# Artemis_Plus.net
KiCad netlist of a schematic drawn in Altium Designer
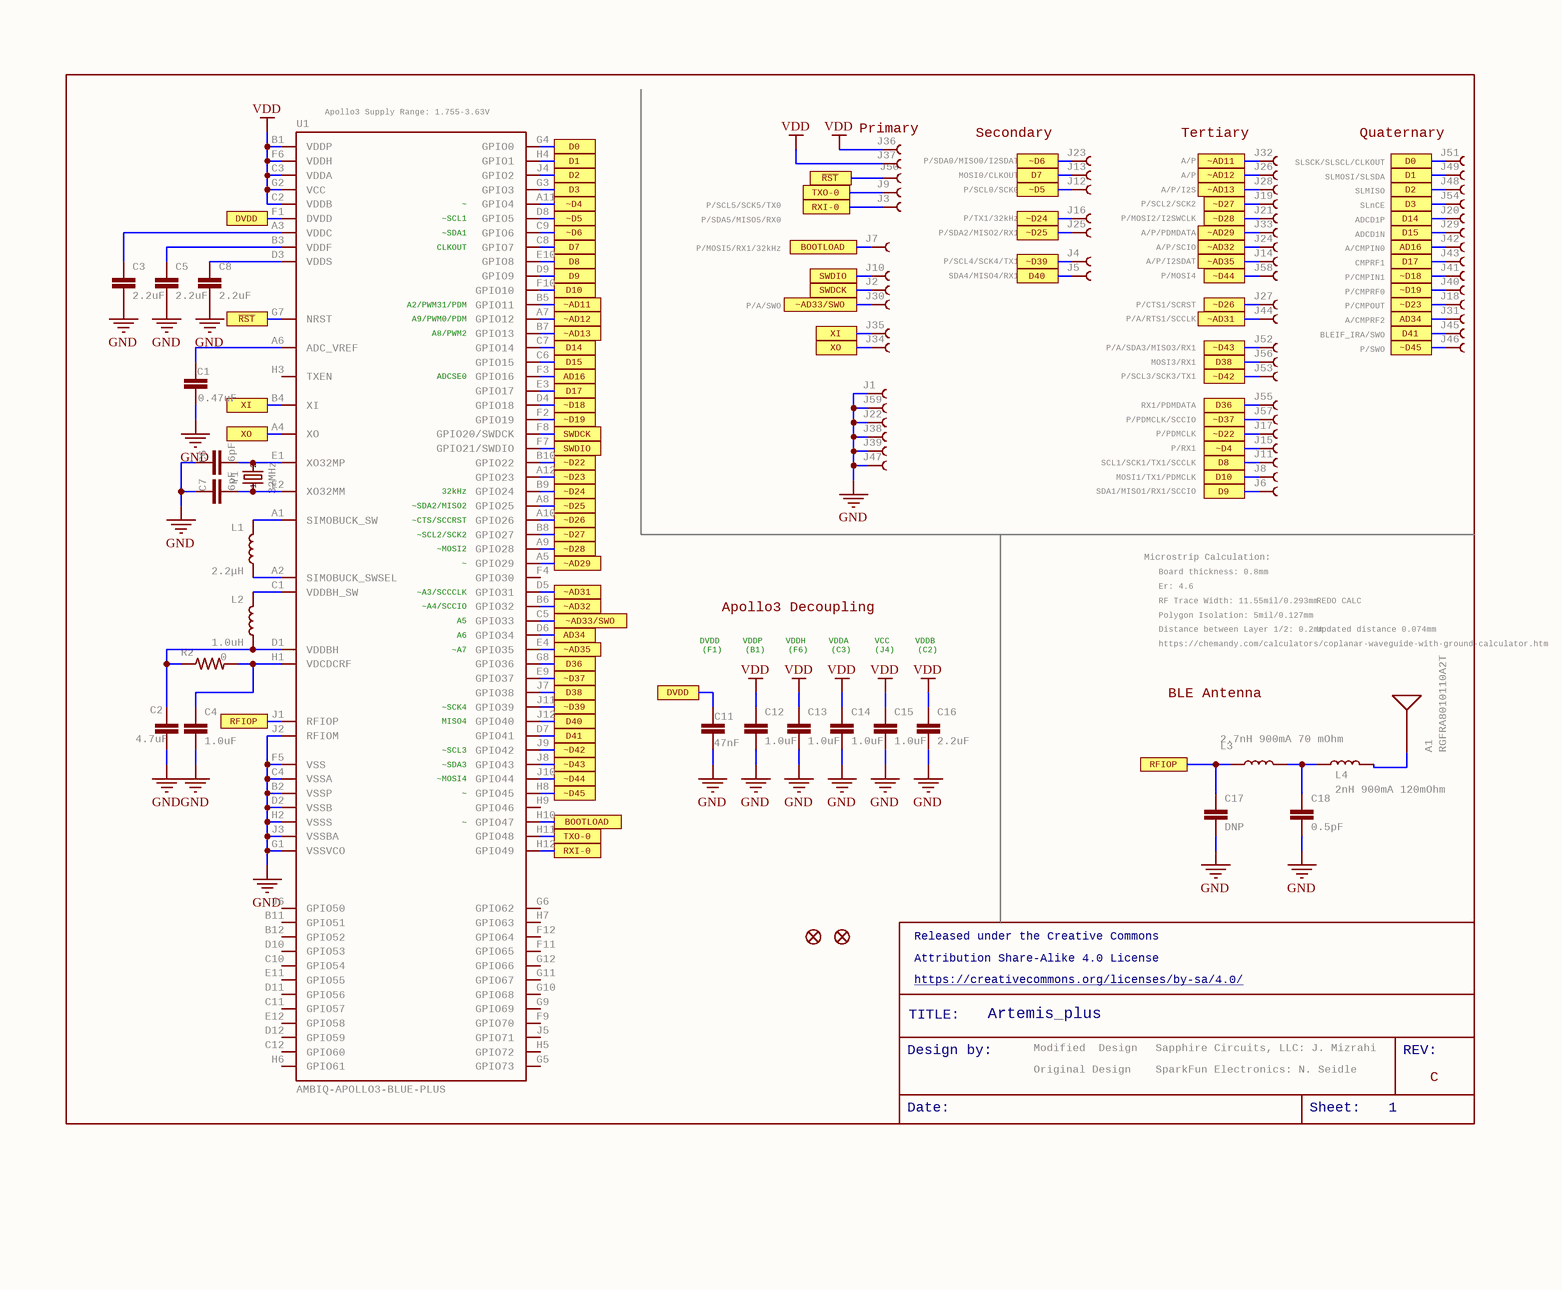
[diagram p0: Artemis_Plus.SchDoc]

(export (version "E")
  (design (tool "Eeschema 10.0.6"))
  (components
    (comp (ref "A1")
      (value "RGFRA8010110A2T")
      (footprint "RGFRA8010110A2T")
      (description "Chip Antenna, 2.45Ghz, Smt Rohs Compliant: Yes ¦Walsin RGFRA8010110A2T")
      (fields (field (name "MANUFACTURER") "Walsin Technologies"))
      (libsource (lib "Artemis_Plus") (part "RGFRA8010110A2T"))
    )
    (comp (ref "C1")
      (value "0.47uF")
      (footprint "0402-TIGHT-C")
      (description "Multilayer Ceramic Capacitor, 0.47 uF, 50 V, ± 2%, C0G (NP0), 0402 [1005 Metric]")
      (fields
        (field (name "MANUFACTURER") "Yageo")
        (field (name "MANUFACTURER PART NUMBER") "CC0402KRX7R6BB474")
      )
      (libsource (lib "Artemis_Plus") (part "CC0402KRX7R6BB474"))
    )
    (comp (ref "C2")
      (value "4.7uF")
      (footprint "0402-TIGHT-C")
      (description "Multilayer Ceramic Capacitor, 4.7 uF, 10 V, ± 20%, X5R, 0402 [1005 Metric]")
      (fields
        (field (name "MANUFACTURER") "Samsung")
        (field (name "MANUFACTURER PART NUMBER") "CL05A475MP5NRNC")
      )
      (libsource (lib "Artemis_Plus") (part "CL05A475MP5NRNC"))
    )
    (comp (ref "C3")
      (value "2.2uF")
      (footprint "0402-TIGHT-C")
      (description "Multilayer Ceramic Capacitor, 2.2 uF, 10 V, ± 10%, X5R, 0402 [1005 Metric]")
      (fields
        (field (name "MANUFACTURER") "Murata")
        (field (name "MANUFACTURER PART NUMBER") "GRM155R61A225KE01D")
      )
      (libsource (lib "Artemis_Plus") (part "GRM155R61A225KE01D"))
    )
    (comp (ref "C4")
      (value "1.0uF")
      (footprint "0402-TIGHT-C")
      (description "Multilayer Ceramic Capacitor, 1 uF, 6.3 V, ± 10%, X7R, 0402 [1005 Metric]")
      (fields
        (field (name "MANUFACTURER") "Murata")
        (field (name "MANUFACTURER PART NUMBER") "GRM155R70J105KA12J")
      )
      (libsource (lib "Artemis_Plus") (part "GRM155R70J105KA12J"))
    )
    (comp (ref "C5")
      (value "2.2uF")
      (footprint "0402-TIGHT-C")
      (description "Multilayer Ceramic Capacitor, 2.2 uF, 10 V, ± 10%, X5R, 0402 [1005 Metric]")
      (fields
        (field (name "MANUFACTURER") "Murata")
        (field (name "MANUFACTURER PART NUMBER") "GRM155R61A225KE01D")
      )
      (libsource (lib "Artemis_Plus") (part "GRM155R61A225KE01D"))
    )
    (comp (ref "C6")
      (value "6pF")
      (footprint "0402-TIGHT-C")
      (description "0402 6 pF 50 V ±0.5 pF Tolerance C0G/NP0 SMT Multilayer Ceramic Capacitor")
      (fields
        (field (name "MANUFACTURER") "Walsin Technologies")
        (field (name "MANUFACTURER PART NUMBER") "0402N6R0D500CT")
      )
      (libsource (lib "Artemis_Plus") (part "0402N6R0D500CT"))
    )
    (comp (ref "C7")
      (value "6pF")
      (footprint "0402-TIGHT-C")
      (description "0402 6 pF 50 V ±0.5 pF Tolerance C0G/NP0 SMT Multilayer Ceramic Capacitor")
      (fields
        (field (name "MANUFACTURER") "Walsin Technologies")
        (field (name "MANUFACTURER PART NUMBER") "0402N6R0D500CT")
      )
      (libsource (lib "Artemis_Plus") (part "0402N6R0D500CT"))
    )
    (comp (ref "C8")
      (value "2.2uF")
      (footprint "0402-TIGHT-C")
      (description "Multilayer Ceramic Capacitor, 2.2 uF, 10 V, ± 10%, X5R, 0402 [1005 Metric]")
      (fields
        (field (name "MANUFACTURER") "Murata")
        (field (name "MANUFACTURER PART NUMBER") "GRM155R61A225KE01D")
      )
      (libsource (lib "Artemis_Plus") (part "GRM155R61A225KE01D"))
    )
    (comp (ref "C11")
      (value "47nF")
      (footprint "0402-TIGHT-C")
      (description "CAP CER 0.047UF 16V 10% X7R 0402")
      (fields
        (field (name "MANUFACTURER") "Murata")
        (field (name "MANUFACTURER PART NUMBER") "GCM155R71C473KA37D")
      )
      (libsource (lib "Artemis_Plus") (part "GCM155R71C473KA37D"))
    )
    (comp (ref "C12")
      (value "1.0uF")
      (footprint "0402-TIGHT-C")
      (description "Multilayer Ceramic Capacitor, 1 uF, 6.3 V, ± 10%, X7R, 0402 [1005 Metric]")
      (fields
        (field (name "MANUFACTURER") "Murata")
        (field (name "MANUFACTURER PART NUMBER") "GRM155R70J105KA12J")
      )
      (libsource (lib "Artemis_Plus") (part "GRM155R70J105KA12J"))
    )
    (comp (ref "C13")
      (value "1.0uF")
      (footprint "0402-TIGHT-C")
      (description "Multilayer Ceramic Capacitor, 1 uF, 6.3 V, ± 10%, X7R, 0402 [1005 Metric]")
      (fields
        (field (name "MANUFACTURER") "Murata")
        (field (name "MANUFACTURER PART NUMBER") "GRM155R70J105KA12J")
      )
      (libsource (lib "Artemis_Plus") (part "GRM155R70J105KA12J"))
    )
    (comp (ref "C14")
      (value "1.0uF")
      (footprint "0402-TIGHT-C")
      (description "Multilayer Ceramic Capacitor, 1 uF, 6.3 V, ± 10%, X7R, 0402 [1005 Metric]")
      (fields
        (field (name "MANUFACTURER") "Murata")
        (field (name "MANUFACTURER PART NUMBER") "GRM155R70J105KA12J")
      )
      (libsource (lib "Artemis_Plus") (part "GRM155R70J105KA12J"))
    )
    (comp (ref "C15")
      (value "1.0uF")
      (footprint "0402-TIGHT-C")
      (description "Multilayer Ceramic Capacitor, 1 uF, 6.3 V, ± 10%, X7R, 0402 [1005 Metric]")
      (fields
        (field (name "MANUFACTURER") "Murata")
        (field (name "MANUFACTURER PART NUMBER") "GRM155R70J105KA12J")
      )
      (libsource (lib "Artemis_Plus") (part "GRM155R70J105KA12J"))
    )
    (comp (ref "C16")
      (value "2.2uF")
      (footprint "0402-TIGHT-C")
      (description "Multilayer Ceramic Capacitor, 2.2 uF, 10 V, ± 10%, X5R, 0402 [1005 Metric]")
      (fields
        (field (name "MANUFACTURER") "Murata")
        (field (name "MANUFACTURER PART NUMBER") "GRM155R61A225KE01D")
      )
      (libsource (lib "Artemis_Plus") (part "GRM155R61A225KE01D"))
    )
    (comp (ref "C17")
      (value "DNP")
      (footprint "0402-TIGHT")
      (libsource (lib "Artemis_Plus") (part "DNP-CAP-0402-TIGHT"))
    )
    (comp (ref "C18")
      (value "0.5pF")
      (footprint "0402-TIGHT-C")
      (description "Multilayer Ceramic Capacitor, 0.5 pF, 50 V, ± 0.25pF, C0G (NP0), 0402 [1005 Metric]")
      (fields
        (field (name "MANUFACTURER") "Murata")
        (field (name "MANUFACTURER PART NUMBER") "GJM1555C1HR50CB01D")
      )
      (libsource (lib "Artemis_Plus") (part "GJM1555C1HR50CB01D"))
    )
    (comp (ref "FD1")
      (value "FIDUCIAL0.4MM")
      (footprint "FIDUCIAL-0.4MM")
      (libsource (lib "Artemis_Plus") (part "FIDUCIAL0.4MM"))
    )
    (comp (ref "FD2")
      (value "FIDUCIAL0.4MM")
      (footprint "FIDUCIAL-0.4MM")
      (libsource (lib "Artemis_Plus") (part "FIDUCIAL0.4MM"))
    )
    (comp (ref "J1")
      (value "PAD.4X.6")
      (footprint "MODULE_PAD")
      (libsource (lib "Artemis_Plus") (part "PAD.4X.6"))
    )
    (comp (ref "J2")
      (value "PAD.4X.6")
      (footprint "MODULE_PAD")
      (libsource (lib "Artemis_Plus") (part "PAD.4X.6"))
    )
    (comp (ref "J3")
      (value "PAD.4X.6")
      (footprint "MODULE_PAD")
      (libsource (lib "Artemis_Plus") (part "PAD.4X.6"))
    )
    (comp (ref "J4")
      (value "PAD.4X.6")
      (footprint "MODULE_PAD")
      (libsource (lib "Artemis_Plus") (part "PAD.4X.6"))
    )
    (comp (ref "J5")
      (value "PAD.4X.6")
      (footprint "MODULE_PAD")
      (libsource (lib "Artemis_Plus") (part "PAD.4X.6"))
    )
    (comp (ref "J6")
      (value "PAD.4X.6")
      (footprint "MODULE_PAD")
      (libsource (lib "Artemis_Plus") (part "PAD.4X.6"))
    )
    (comp (ref "J7")
      (value "PAD.4X.6")
      (footprint "MODULE_PAD")
      (libsource (lib "Artemis_Plus") (part "PAD.4X.6"))
    )
    (comp (ref "J8")
      (value "PAD.4X.6")
      (footprint "MODULE_PAD")
      (libsource (lib "Artemis_Plus") (part "PAD.4X.6"))
    )
    (comp (ref "J9")
      (value "PAD.4X.6")
      (footprint "MODULE_PAD")
      (libsource (lib "Artemis_Plus") (part "PAD.4X.6"))
    )
    (comp (ref "J10")
      (value "PAD.4X.6")
      (footprint "MODULE_PAD")
      (libsource (lib "Artemis_Plus") (part "PAD.4X.6"))
    )
    (comp (ref "J11")
      (value "PAD.4X.6")
      (footprint "MODULE_PAD")
      (libsource (lib "Artemis_Plus") (part "PAD.4X.6"))
    )
    (comp (ref "J12")
      (value "PAD.4X.6")
      (footprint "MODULE_PAD")
      (libsource (lib "Artemis_Plus") (part "PAD.4X.6"))
    )
    (comp (ref "J13")
      (value "PAD.4X.6")
      (footprint "MODULE_PAD")
      (libsource (lib "Artemis_Plus") (part "PAD.4X.6"))
    )
    (comp (ref "J14")
      (value "PAD.4X.6")
      (footprint "MODULE_PAD")
      (libsource (lib "Artemis_Plus") (part "PAD.4X.6"))
    )
    (comp (ref "J15")
      (value "PAD.4X.6")
      (footprint "MODULE_PAD")
      (libsource (lib "Artemis_Plus") (part "PAD.4X.6"))
    )
    (comp (ref "J16")
      (value "PAD.4X.6")
      (footprint "MODULE_PAD")
      (libsource (lib "Artemis_Plus") (part "PAD.4X.6"))
    )
    (comp (ref "J17")
      (value "PAD.4X.6")
      (footprint "MODULE_PAD")
      (libsource (lib "Artemis_Plus") (part "PAD.4X.6"))
    )
    (comp (ref "J18")
      (value "PAD.4X.6")
      (footprint "MODULE_PAD")
      (libsource (lib "Artemis_Plus") (part "PAD.4X.6"))
    )
    (comp (ref "J19")
      (value "PAD.4X.6")
      (footprint "MODULE_PAD")
      (libsource (lib "Artemis_Plus") (part "PAD.4X.6"))
    )
    (comp (ref "J20")
      (value "PAD.4X.6")
      (footprint "MODULE_PAD")
      (libsource (lib "Artemis_Plus") (part "PAD.4X.6"))
    )
    (comp (ref "J21")
      (value "PAD.4X.6")
      (footprint "MODULE_PAD")
      (libsource (lib "Artemis_Plus") (part "PAD.4X.6"))
    )
    (comp (ref "J22")
      (value "~")
      (footprint "MODULE_MINI_PAD")
      (libsource (lib "Artemis_Plus") (part "PAD.6X.6"))
    )
    (comp (ref "J23")
      (value "PAD.4X.6")
      (footprint "MODULE_PAD")
      (libsource (lib "Artemis_Plus") (part "PAD.4X.6"))
    )
    (comp (ref "J24")
      (value "PAD.4X.6")
      (footprint "MODULE_PAD")
      (libsource (lib "Artemis_Plus") (part "PAD.4X.6"))
    )
    (comp (ref "J25")
      (value "PAD.4X.6")
      (footprint "MODULE_PAD")
      (libsource (lib "Artemis_Plus") (part "PAD.4X.6"))
    )
    (comp (ref "J26")
      (value "PAD.4X.6")
      (footprint "MODULE_PAD")
      (libsource (lib "Artemis_Plus") (part "PAD.4X.6"))
    )
    (comp (ref "J27")
      (value "PAD.4X.6")
      (footprint "MODULE_PAD")
      (libsource (lib "Artemis_Plus") (part "PAD.4X.6"))
    )
    (comp (ref "J28")
      (value "PAD.4X.6")
      (footprint "MODULE_PAD")
      (libsource (lib "Artemis_Plus") (part "PAD.4X.6"))
    )
    (comp (ref "J29")
      (value "PAD.4X.6")
      (footprint "MODULE_PAD")
      (libsource (lib "Artemis_Plus") (part "PAD.4X.6"))
    )
    (comp (ref "J30")
      (value "PAD.4X.6")
      (footprint "MODULE_PAD")
      (libsource (lib "Artemis_Plus") (part "PAD.4X.6"))
    )
    (comp (ref "J31")
      (value "PAD.4X.6")
      (footprint "MODULE_PAD")
      (libsource (lib "Artemis_Plus") (part "PAD.4X.6"))
    )
    (comp (ref "J32")
      (value "PAD.4X.6")
      (footprint "MODULE_PAD")
      (libsource (lib "Artemis_Plus") (part "PAD.4X.6"))
    )
    (comp (ref "J33")
      (value "PAD.4X.6")
      (footprint "MODULE_PAD")
      (libsource (lib "Artemis_Plus") (part "PAD.4X.6"))
    )
    (comp (ref "J34")
      (value "PAD.4X.6")
      (footprint "MODULE_PAD")
      (libsource (lib "Artemis_Plus") (part "PAD.4X.6"))
    )
    (comp (ref "J35")
      (value "PAD.4X.6")
      (footprint "MODULE_PAD")
      (libsource (lib "Artemis_Plus") (part "PAD.4X.6"))
    )
    (comp (ref "J36")
      (value "PAD.4X.6")
      (footprint "MODULE_PAD")
      (libsource (lib "Artemis_Plus") (part "PAD.4X.6"))
    )
    (comp (ref "J37")
      (value "PAD.4X.6")
      (footprint "MODULE_PAD")
      (libsource (lib "Artemis_Plus") (part "PAD.4X.6"))
    )
    (comp (ref "J38")
      (value "PAD.6X.6")
      (footprint "MODULE_MINI_PAD")
      (libsource (lib "Artemis_Plus") (part "PAD.6X.6"))
    )
    (comp (ref "J39")
      (value "PAD.4X.6")
      (footprint "MODULE_PAD")
      (libsource (lib "Artemis_Plus") (part "PAD.4X.6"))
    )
    (comp (ref "J40")
      (value "PAD.4X.6")
      (footprint "MODULE_PAD")
      (libsource (lib "Artemis_Plus") (part "PAD.4X.6"))
    )
    (comp (ref "J41")
      (value "PAD.4X.6")
      (footprint "MODULE_PAD")
      (libsource (lib "Artemis_Plus") (part "PAD.4X.6"))
    )
    (comp (ref "J42")
      (value "PAD.4X.6")
      (footprint "MODULE_PAD")
      (libsource (lib "Artemis_Plus") (part "PAD.4X.6"))
    )
    (comp (ref "J43")
      (value "PAD.4X.6")
      (footprint "MODULE_PAD")
      (libsource (lib "Artemis_Plus") (part "PAD.4X.6"))
    )
    (comp (ref "J44")
      (value "PAD.4X.6")
      (footprint "MODULE_PAD")
      (libsource (lib "Artemis_Plus") (part "PAD.4X.6"))
    )
    (comp (ref "J45")
      (value "PAD.4X.6")
      (footprint "MODULE_PAD")
      (libsource (lib "Artemis_Plus") (part "PAD.4X.6"))
    )
    (comp (ref "J46")
      (value "PAD.4X.6")
      (footprint "MODULE_PAD")
      (libsource (lib "Artemis_Plus") (part "PAD.4X.6"))
    )
    (comp (ref "J47")
      (value "PAD.4X.6")
      (footprint "MODULE_PAD")
      (libsource (lib "Artemis_Plus") (part "PAD.4X.6"))
    )
    (comp (ref "J48")
      (value "PAD.4X.6")
      (footprint "MODULE_PAD")
      (libsource (lib "Artemis_Plus") (part "PAD.4X.6"))
    )
    (comp (ref "J49")
      (value "PAD.4X.6")
      (footprint "MODULE_PAD")
      (libsource (lib "Artemis_Plus") (part "PAD.4X.6"))
    )
    (comp (ref "J50")
      (value "PAD.4X.6")
      (footprint "MODULE_PAD")
      (libsource (lib "Artemis_Plus") (part "PAD.4X.6"))
    )
    (comp (ref "J51")
      (value "PAD.4X.6")
      (footprint "MODULE_PAD")
      (libsource (lib "Artemis_Plus") (part "PAD.4X.6"))
    )
    (comp (ref "J52")
      (value "PAD.4X.6")
      (footprint "MODULE_PAD")
      (libsource (lib "Artemis_Plus") (part "PAD.4X.6"))
    )
    (comp (ref "J53")
      (value "PAD.4X.6")
      (footprint "MODULE_PAD")
      (libsource (lib "Artemis_Plus") (part "PAD.4X.6"))
    )
    (comp (ref "J54")
      (value "PAD.4X.6")
      (footprint "MODULE_PAD")
      (libsource (lib "Artemis_Plus") (part "PAD.4X.6"))
    )
    (comp (ref "J55")
      (value "PAD.4X.6")
      (footprint "MODULE_PAD")
      (libsource (lib "Artemis_Plus") (part "PAD.4X.6"))
    )
    (comp (ref "J56")
      (value "PAD.4X.6")
      (footprint "MODULE_PAD")
      (libsource (lib "Artemis_Plus") (part "PAD.4X.6"))
    )
    (comp (ref "J57")
      (value "PAD.4X.6")
      (footprint "MODULE_PAD")
      (libsource (lib "Artemis_Plus") (part "PAD.4X.6"))
    )
    (comp (ref "J58")
      (value "PAD.4X.6")
      (footprint "MODULE_PAD")
      (libsource (lib "Artemis_Plus") (part "PAD.4X.6"))
    )
    (comp (ref "J59")
      (value "PAD.4X.6")
      (footprint "MODULE_PAD")
      (libsource (lib "Artemis_Plus") (part "PAD.4X.6"))
    )
    (comp (ref "L1")
      (value "2.2μH")
      (footprint "DFE201610E-2R2MP2")
      (description "Inductor Power Shielded Wirewound 2.2uH 20% 1MHz Metal 1.7A 0.14Ohm DCR 0806 T/R")
      (fields
        (field (name "MANUFACTURER") "Murata")
        (field (name "MANUFACTURER PART NUMBER") "DFE201610E-2R2M=P2")
      )
      (libsource (lib "Artemis_Plus") (part "DFE201610E-2R2M=P2"))
    )
    (comp (ref "L2")
      (value "1.0uH")
      (footprint "LQM21PN1R0MEHD")
      (description "Inductor Power Chip Shielded Multi-Layer 1uH 20% 1MHz Ferrite 1.6A 0.107Ohm DCR 0805 T/R")
      (fields
        (field (name "MANUFACTURER") "Murata")
        (field (name "MANUFACTURER PART NUMBER") "LQM21PN1R0MEHD")
      )
      (libsource (lib "Artemis_Plus") (part "LQM21PN1R0MEHD"))
    )
    (comp (ref "L3")
      (value "2.7nH 900mA 70 mOhm")
      (footprint "0402-TIGHT-L")
      (description "IND 2.7NH 900MA 70 MOHM")
      (fields
        (field (name "MANUFACTURER") "Murata")
        (field (name "MANUFACTURER PART NUMBER") "LQG15WZ2N7S02D")
      )
      (libsource (lib "Artemis_Plus") (part "LQG15WZ2N7S02D"))
    )
    (comp (ref "L4")
      (value "2nH 900mA 120mOhm")
      (footprint "0402-TIGHT-L")
      (description "FIXED IND 2NH 900MA 120 MOHM SMD")
      (fields
        (field (name "MANUFACTURER") "Murata")
        (field (name "MANUFACTURER PART NUMBER") "LQG15HN2N0S02D")
      )
      (libsource (lib "Artemis_Plus") (part "LQG15HN2N0S02D"))
    )
    (comp (ref "R2")
      (value "0")
      (footprint "0402-TIGHT-R")
      (description "Res Thick Film 0402 0 Ohm Jumper Molded SMD Paper T/R")
      (fields
        (field (name "MANUFACTURER") "Stackpole Electronics")
        (field (name "MANUFACTURER PART NUMBER") "RMCF0402ZT0R00")
      )
      (libsource (lib "Artemis_Plus") (part "RMCF0402ZT0R00"))
    )
    (comp (ref "U1")
      (value "AMBIQ-APOLLO3-BLUE-PLUS")
      (footprint "BGA-104-5.3X4.3MM - Sprite-mixed-0.2-0.19 - 3DModel")
      (description "Apollo3 Blue Plus 96 MHz Cortex M4F, 2048 KB Flash, 768 KB RAM, BLE 5, BGA")
      (fields
        (field (name "MANUFACTURER") "Ambiq Micro")
        (field (name "MANUFACTURER PART NUMBER") "AMA3B2KK-KBR")
      )
      (libsource (lib "Artemis_Plus") (part "AMA3B2KK-KBR"))
    )
    (comp (ref "Y1")
      (value "32MHz")
      (footprint "ECS-320-6-37B2-CKM-TR")
      (description "Crystal 32 Mhz 6PF SMD")
      (fields
        (field (name "MANUFACTURER") "ECS International")
        (field (name "MANUFACTURER PART NUMBER") "ECS-320-6-37B2-CKM-TR")
        (field (name "1") "1")
        (field (name "2") "2")
      )
      (libsource (lib "Artemis_Plus") (part "ECS-320-6-37B2-CKM-TR"))
    )
  )
  (nets
    (net (code "1") (name "/AD16") (class "Default")
      (node (ref "J42") (pin "1") (pinfunction "1_1") (pintype "bidirectional"))
      (node (ref "U1") (pin "F3") (pinfunction "GPIO16_F3") (pintype "bidirectional"))
    )
    (net (code "2") (name "/AD34") (class "Default")
      (node (ref "J31") (pin "1") (pinfunction "1_1") (pintype "bidirectional"))
      (node (ref "U1") (pin "D6") (pinfunction "GPIO34_D6") (pintype "bidirectional"))
    )
    (net (code "3") (name "/BOOTLOAD") (class "Default")
      (node (ref "J7") (pin "1") (pinfunction "1_1") (pintype "bidirectional"))
      (node (ref "U1") (pin "H10") (pinfunction "GPIO47_H10") (pintype "bidirectional"))
    )
    (net (code "4") (name "/D0") (class "Default")
      (node (ref "J51") (pin "1") (pinfunction "1_1") (pintype "bidirectional"))
      (node (ref "U1") (pin "G4") (pinfunction "GPIO0_G4") (pintype "bidirectional"))
    )
    (net (code "5") (name "/D1") (class "Default")
      (node (ref "J49") (pin "1") (pinfunction "1_1") (pintype "bidirectional"))
      (node (ref "U1") (pin "H4") (pinfunction "GPIO1_H4") (pintype "bidirectional"))
    )
    (net (code "6") (name "/D2") (class "Default")
      (node (ref "J48") (pin "1") (pinfunction "1_1") (pintype "bidirectional"))
      (node (ref "U1") (pin "J4") (pinfunction "GPIO2_J4") (pintype "bidirectional"))
    )
    (net (code "7") (name "/D3") (class "Default")
      (node (ref "J54") (pin "1") (pinfunction "1_1") (pintype "bidirectional"))
      (node (ref "U1") (pin "G3") (pinfunction "GPIO3_G3") (pintype "bidirectional"))
    )
    (net (code "8") (name "/D7") (class "Default")
      (node (ref "J13") (pin "1") (pinfunction "1_1") (pintype "bidirectional"))
      (node (ref "U1") (pin "C8") (pinfunction "GPIO7_C8") (pintype "bidirectional"))
    )
    (net (code "9") (name "/D8") (class "Default")
      (node (ref "J11") (pin "1") (pinfunction "1_1") (pintype "bidirectional"))
      (node (ref "U1") (pin "E10") (pinfunction "GPIO8_E10") (pintype "bidirectional"))
    )
    (net (code "10") (name "/D9") (class "Default")
      (node (ref "J6") (pin "1") (pinfunction "1_1") (pintype "bidirectional"))
      (node (ref "U1") (pin "D9") (pinfunction "GPIO9_D9") (pintype "bidirectional"))
    )
    (net (code "11") (name "/D10") (class "Default")
      (node (ref "J8") (pin "1") (pinfunction "1_1") (pintype "bidirectional"))
      (node (ref "U1") (pin "F10") (pinfunction "GPIO10_F10") (pintype "bidirectional"))
    )
    (net (code "12") (name "/D14") (class "Default")
      (node (ref "J20") (pin "1") (pinfunction "1_1") (pintype "bidirectional"))
      (node (ref "U1") (pin "C7") (pinfunction "GPIO14_C7") (pintype "bidirectional"))
    )
    (net (code "13") (name "/D15") (class "Default")
      (node (ref "J29") (pin "1") (pinfunction "1_1") (pintype "bidirectional"))
      (node (ref "U1") (pin "C6") (pinfunction "GPIO15_C6") (pintype "bidirectional"))
    )
    (net (code "14") (name "/D17") (class "Default")
      (node (ref "J43") (pin "1") (pinfunction "1_1") (pintype "bidirectional"))
      (node (ref "U1") (pin "E3") (pinfunction "GPIO17_E3") (pintype "bidirectional"))
    )
    (net (code "15") (name "/D36") (class "Default")
      (node (ref "J55") (pin "1") (pinfunction "1_1") (pintype "bidirectional"))
      (node (ref "U1") (pin "G8") (pinfunction "GPIO36_G8") (pintype "bidirectional"))
    )
    (net (code "16") (name "/D38") (class "Default")
      (node (ref "J56") (pin "1") (pinfunction "1_1") (pintype "bidirectional"))
      (node (ref "U1") (pin "J7") (pinfunction "GPIO38_J7") (pintype "bidirectional"))
    )
    (net (code "17") (name "/D40") (class "Default")
      (node (ref "J5") (pin "1") (pinfunction "1_1") (pintype "bidirectional"))
      (node (ref "U1") (pin "J12") (pinfunction "GPIO40_J12") (pintype "bidirectional"))
    )
    (net (code "18") (name "/D41") (class "Default")
      (node (ref "J45") (pin "1") (pinfunction "1_1") (pintype "bidirectional"))
      (node (ref "U1") (pin "D7") (pinfunction "GPIO41_D7") (pintype "bidirectional"))
    )
    (net (code "19") (name "/DVDD") (class "Default")
      (node (ref "C11") (pin "1") (pinfunction "1_1") (pintype "passive"))
      (node (ref "U1") (pin "F1") (pinfunction "DVDD_F1") (pintype "bidirectional"))
    )
    (net (code "20") (name "/RFIOP") (class "Default")
      (node (ref "C17") (pin "1") (pinfunction "1_1") (pintype "passive"))
      (node (ref "L3") (pin "1") (pinfunction "1_1") (pintype "passive"))
      (node (ref "U1") (pin "J1") (pinfunction "RFIOP_J1") (pintype "bidirectional"))
    )
    (net (code "21") (name "/RXI-0") (class "Default")
      (node (ref "J3") (pin "1") (pinfunction "1_1") (pintype "bidirectional"))
      (node (ref "U1") (pin "H12") (pinfunction "GPIO49_H12") (pintype "bidirectional"))
    )
    (net (code "22") (name "/SWDCK") (class "Default")
      (node (ref "J2") (pin "1") (pinfunction "1_1") (pintype "bidirectional"))
      (node (ref "U1") (pin "F8") (pinfunction "GPIO20/SWDCK_F8") (pintype "bidirectional"))
    )
    (net (code "23") (name "/SWDIO") (class "Default")
      (node (ref "J10") (pin "1") (pinfunction "1_1") (pintype "bidirectional"))
      (node (ref "U1") (pin "F7") (pinfunction "GPIO21/SWDIO_F7") (pintype "bidirectional"))
    )
    (net (code "24") (name "/TXO-0") (class "Default")
      (node (ref "J9") (pin "1") (pinfunction "1_1") (pintype "bidirectional"))
      (node (ref "U1") (pin "H11") (pinfunction "GPIO48_H11") (pintype "bidirectional"))
    )
    (net (code "25") (name "/XI") (class "Default")
      (node (ref "J35") (pin "1") (pinfunction "1_1") (pintype "bidirectional"))
      (node (ref "U1") (pin "B4") (pinfunction "XI_B4") (pintype "bidirectional"))
    )
    (net (code "26") (name "/XO") (class "Default")
      (node (ref "J34") (pin "1") (pinfunction "1_1") (pintype "bidirectional"))
      (node (ref "U1") (pin "A4") (pinfunction "XO_A4") (pintype "bidirectional"))
    )
    (net (code "27") (name "/~AD11") (class "Default")
      (node (ref "J32") (pin "1") (pinfunction "1_1") (pintype "bidirectional"))
      (node (ref "U1") (pin "B5") (pinfunction "GPIO11_B5") (pintype "bidirectional"))
    )
    (net (code "28") (name "/~AD12") (class "Default")
      (node (ref "J26") (pin "1") (pinfunction "1_1") (pintype "bidirectional"))
      (node (ref "U1") (pin "A7") (pinfunction "GPIO12_A7") (pintype "bidirectional"))
    )
    (net (code "29") (name "/~AD13") (class "Default")
      (node (ref "J28") (pin "1") (pinfunction "1_1") (pintype "bidirectional"))
      (node (ref "U1") (pin "B7") (pinfunction "GPIO13_B7") (pintype "bidirectional"))
    )
    (net (code "30") (name "/~AD29") (class "Default")
      (node (ref "J33") (pin "1") (pinfunction "1_1") (pintype "bidirectional"))
      (node (ref "U1") (pin "A5") (pinfunction "GPIO29_A5") (pintype "bidirectional"))
    )
    (net (code "31") (name "/~AD31") (class "Default")
      (node (ref "J44") (pin "1") (pinfunction "1_1") (pintype "bidirectional"))
      (node (ref "U1") (pin "D5") (pinfunction "GPIO31_D5") (pintype "bidirectional"))
    )
    (net (code "32") (name "/~AD32") (class "Default")
      (node (ref "J24") (pin "1") (pinfunction "1_1") (pintype "bidirectional"))
      (node (ref "U1") (pin "B6") (pinfunction "GPIO32_B6") (pintype "bidirectional"))
    )
    (net (code "33") (name "/~AD33{slash}SWO") (class "Default")
      (node (ref "J30") (pin "1") (pinfunction "1_1") (pintype "bidirectional"))
      (node (ref "U1") (pin "C5") (pinfunction "GPIO33_C5") (pintype "bidirectional"))
    )
    (net (code "34") (name "/~AD35") (class "Default")
      (node (ref "J14") (pin "1") (pinfunction "1_1") (pintype "bidirectional"))
      (node (ref "U1") (pin "E4") (pinfunction "GPIO35_E4") (pintype "bidirectional"))
    )
    (net (code "35") (name "/~D4") (class "Default")
      (node (ref "J15") (pin "1") (pinfunction "1_1") (pintype "bidirectional"))
      (node (ref "U1") (pin "A11") (pinfunction "GPIO4_A11") (pintype "bidirectional"))
    )
    (net (code "36") (name "/~D5") (class "Default")
      (node (ref "J12") (pin "1") (pinfunction "1_1") (pintype "bidirectional"))
      (node (ref "U1") (pin "D8") (pinfunction "GPIO5_D8") (pintype "bidirectional"))
    )
    (net (code "37") (name "/~D6") (class "Default")
      (node (ref "J23") (pin "1") (pinfunction "1_1") (pintype "bidirectional"))
      (node (ref "U1") (pin "C9") (pinfunction "GPIO6_C9") (pintype "bidirectional"))
    )
    (net (code "38") (name "/~D18") (class "Default")
      (node (ref "J41") (pin "1") (pinfunction "1_1") (pintype "bidirectional"))
      (node (ref "U1") (pin "D4") (pinfunction "GPIO18_D4") (pintype "bidirectional"))
    )
    (net (code "39") (name "/~D19") (class "Default")
      (node (ref "J40") (pin "1") (pinfunction "1_1") (pintype "bidirectional"))
      (node (ref "U1") (pin "F2") (pinfunction "GPIO19_F2") (pintype "bidirectional"))
    )
    (net (code "40") (name "/~D22") (class "Default")
      (node (ref "J17") (pin "1") (pinfunction "1_1") (pintype "bidirectional"))
      (node (ref "U1") (pin "B10") (pinfunction "GPIO22_B10") (pintype "bidirectional"))
    )
    (net (code "41") (name "/~D23") (class "Default")
      (node (ref "J18") (pin "1") (pinfunction "1_1") (pintype "bidirectional"))
      (node (ref "U1") (pin "A12") (pinfunction "GPIO23_A12") (pintype "bidirectional"))
    )
    (net (code "42") (name "/~D24") (class "Default")
      (node (ref "J16") (pin "1") (pinfunction "1_1") (pintype "bidirectional"))
      (node (ref "U1") (pin "B9") (pinfunction "GPIO24_B9") (pintype "bidirectional"))
    )
    (net (code "43") (name "/~D25") (class "Default")
      (node (ref "J25") (pin "1") (pinfunction "1_1") (pintype "bidirectional"))
      (node (ref "U1") (pin "A8") (pinfunction "GPIO25_A8") (pintype "bidirectional"))
    )
    (net (code "44") (name "/~D26") (class "Default")
      (node (ref "J27") (pin "1") (pinfunction "1_1") (pintype "bidirectional"))
      (node (ref "U1") (pin "A10") (pinfunction "GPIO26_A10") (pintype "bidirectional"))
    )
    (net (code "45") (name "/~D27") (class "Default")
      (node (ref "J19") (pin "1") (pinfunction "1_1") (pintype "bidirectional"))
      (node (ref "U1") (pin "B8") (pinfunction "GPIO27_B8") (pintype "bidirectional"))
    )
    (net (code "46") (name "/~D28") (class "Default")
      (node (ref "J21") (pin "1") (pinfunction "1_1") (pintype "bidirectional"))
      (node (ref "U1") (pin "A9") (pinfunction "GPIO28_A9") (pintype "bidirectional"))
    )
    (net (code "47") (name "/~D37") (class "Default")
      (node (ref "J57") (pin "1") (pinfunction "1_1") (pintype "bidirectional"))
      (node (ref "U1") (pin "E9") (pinfunction "GPIO37_E9") (pintype "bidirectional"))
    )
    (net (code "48") (name "/~D39") (class "Default")
      (node (ref "J4") (pin "1") (pinfunction "1_1") (pintype "bidirectional"))
      (node (ref "U1") (pin "J11") (pinfunction "GPIO39_J11") (pintype "bidirectional"))
    )
    (net (code "49") (name "/~D42") (class "Default")
      (node (ref "J53") (pin "1") (pinfunction "1_1") (pintype "bidirectional"))
      (node (ref "U1") (pin "J9") (pinfunction "GPIO42_J9") (pintype "bidirectional"))
    )
    (net (code "50") (name "/~D43") (class "Default")
      (node (ref "J52") (pin "1") (pinfunction "1_1") (pintype "bidirectional"))
      (node (ref "U1") (pin "J8") (pinfunction "GPIO43_J8") (pintype "bidirectional"))
    )
    (net (code "51") (name "/~D44") (class "Default")
      (node (ref "J58") (pin "1") (pinfunction "1_1") (pintype "bidirectional"))
      (node (ref "U1") (pin "J10") (pinfunction "GPIO44_J10") (pintype "bidirectional"))
    )
    (net (code "52") (name "/~D45") (class "Default")
      (node (ref "J46") (pin "1") (pinfunction "1_1") (pintype "bidirectional"))
      (node (ref "U1") (pin "H8") (pinfunction "GPIO45_H8") (pintype "bidirectional"))
    )
    (net (code "53") (name "/~{RST}") (class "Default")
      (node (ref "J50") (pin "1") (pinfunction "1_1") (pintype "bidirectional"))
      (node (ref "U1") (pin "G7") (pinfunction "NRST_G7") (pintype "bidirectional"))
    )
    (net (code "54") (name "GND") (class "Default")
      (node (ref "C1") (pin "2") (pinfunction "2_2") (pintype "passive"))
      (node (ref "C11") (pin "2") (pinfunction "2_2") (pintype "passive"))
      (node (ref "C12") (pin "2") (pinfunction "2_2") (pintype "passive"))
      (node (ref "C13") (pin "2") (pinfunction "2_2") (pintype "passive"))
      (node (ref "C14") (pin "2") (pinfunction "2_2") (pintype "passive"))
      (node (ref "C15") (pin "2") (pinfunction "2_2") (pintype "passive"))
      (node (ref "C16") (pin "2") (pinfunction "2_2") (pintype "passive"))
      (node (ref "C17") (pin "2") (pinfunction "2_2") (pintype "passive"))
      (node (ref "C18") (pin "2") (pinfunction "2_2") (pintype "passive"))
      (node (ref "C2") (pin "2") (pinfunction "2_2") (pintype "passive"))
      (node (ref "C3") (pin "2") (pinfunction "2_2") (pintype "passive"))
      (node (ref "C4") (pin "2") (pinfunction "2_2") (pintype "passive"))
      (node (ref "C5") (pin "2") (pinfunction "2_2") (pintype "passive"))
      (node (ref "C6") (pin "1") (pinfunction "1_1") (pintype "passive"))
      (node (ref "C7") (pin "1") (pinfunction "1_1") (pintype "passive"))
      (node (ref "C8") (pin "2") (pinfunction "2_2") (pintype "passive"))
      (node (ref "J1") (pin "1") (pinfunction "1_1") (pintype "bidirectional"))
      (node (ref "J22") (pin "1") (pinfunction "1_1") (pintype "bidirectional"))
      (node (ref "J38") (pin "1") (pinfunction "1_1") (pintype "bidirectional"))
      (node (ref "J39") (pin "1") (pinfunction "1_1") (pintype "bidirectional"))
      (node (ref "J47") (pin "1") (pinfunction "1_1") (pintype "bidirectional"))
      (node (ref "J59") (pin "1") (pinfunction "1_1") (pintype "bidirectional"))
      (node (ref "U1") (pin "B2") (pinfunction "VSSP_B2") (pintype "bidirectional"))
      (node (ref "U1") (pin "C4") (pinfunction "VSSA_C4") (pintype "bidirectional"))
      (node (ref "U1") (pin "D2") (pinfunction "VSSB_D2") (pintype "bidirectional"))
      (node (ref "U1") (pin "F5") (pinfunction "VSS_F5") (pintype "bidirectional"))
      (node (ref "U1") (pin "G1") (pinfunction "VSSVCO_G1") (pintype "bidirectional"))
      (node (ref "U1") (pin "H2") (pinfunction "VSSS_H2") (pintype "bidirectional"))
      (node (ref "U1") (pin "J2") (pinfunction "RFIOM_J2") (pintype "bidirectional"))
      (node (ref "U1") (pin "J3") (pinfunction "VSSBA_J3") (pintype "bidirectional"))
    )
    (net (code "55") (name "Net-(A1-SIGNAL)") (class "Default")
      (node (ref "A1") (pin "FEED") (pinfunction "SIGNAL_FEED") (pintype "bidirectional"))
      (node (ref "L4") (pin "2") (pinfunction "2_2") (pintype "passive"))
    )
    (net (code "56") (name "Net-(C18-Pad1)") (class "Default")
      (node (ref "C18") (pin "1") (pinfunction "1_1") (pintype "passive"))
      (node (ref "L3") (pin "2") (pinfunction "2_2") (pintype "passive"))
      (node (ref "L4") (pin "1") (pinfunction "1_1") (pintype "passive"))
    )
    (net (code "57") (name "Net-(U1-ADC_VREF)") (class "Default")
      (node (ref "C1") (pin "1") (pinfunction "1_1") (pintype "passive"))
      (node (ref "U1") (pin "A6") (pinfunction "ADC_VREF_A6") (pintype "bidirectional"))
    )
    (net (code "58") (name "Net-(U1-SIMOBUCK_SW)") (class "Default")
      (node (ref "L1") (pin "1") (pinfunction "1_1") (pintype "passive"))
      (node (ref "U1") (pin "A1") (pinfunction "SIMOBUCK_SW_A1") (pintype "bidirectional"))
    )
    (net (code "59") (name "Net-(U1-SIMOBUCK_SWSEL)") (class "Default")
      (node (ref "L1") (pin "2") (pinfunction "2_2") (pintype "passive"))
      (node (ref "U1") (pin "A2") (pinfunction "SIMOBUCK_SWSEL_A2") (pintype "bidirectional"))
    )
    (net (code "60") (name "Net-(U1-VDCDCRF)") (class "Default")
      (node (ref "C4") (pin "1") (pinfunction "1_1") (pintype "passive"))
      (node (ref "R2") (pin "2") (pinfunction "2_2") (pintype "passive"))
      (node (ref "U1") (pin "H1") (pinfunction "VDCDCRF_H1") (pintype "bidirectional"))
    )
    (net (code "61") (name "Net-(U1-VDDBH)") (class "Default")
      (node (ref "C2") (pin "1") (pinfunction "1_1") (pintype "passive"))
      (node (ref "L2") (pin "2") (pinfunction "2_2") (pintype "passive"))
      (node (ref "R2") (pin "1") (pinfunction "1_1") (pintype "passive"))
      (node (ref "U1") (pin "D1") (pinfunction "VDDBH_D1") (pintype "bidirectional"))
    )
    (net (code "62") (name "Net-(U1-VDDBH_SW)") (class "Default")
      (node (ref "L2") (pin "1") (pinfunction "1_1") (pintype "passive"))
      (node (ref "U1") (pin "C1") (pinfunction "VDDBH_SW_C1") (pintype "bidirectional"))
    )
    (net (code "63") (name "Net-(U1-VDDC)") (class "Default")
      (node (ref "C3") (pin "1") (pinfunction "1_1") (pintype "passive"))
      (node (ref "U1") (pin "A3") (pinfunction "VDDC_A3") (pintype "bidirectional"))
    )
    (net (code "64") (name "Net-(U1-VDDF)") (class "Default")
      (node (ref "C5") (pin "1") (pinfunction "1_1") (pintype "passive"))
      (node (ref "U1") (pin "B3") (pinfunction "VDDF_B3") (pintype "bidirectional"))
    )
    (net (code "65") (name "Net-(U1-VDDS)") (class "Default")
      (node (ref "C8") (pin "1") (pinfunction "1_1") (pintype "passive"))
      (node (ref "U1") (pin "D3") (pinfunction "VDDS_D3") (pintype "bidirectional"))
    )
    (net (code "66") (name "Net-(U1-XO32MM)") (class "Default")
      (node (ref "C7") (pin "2") (pinfunction "2_2") (pintype "passive"))
      (node (ref "U1") (pin "E2") (pinfunction "XO32MM_E2") (pintype "bidirectional"))
      (node (ref "Y1") (pin "1") (pinfunction "1_1") (pintype "passive"))
    )
    (net (code "67") (name "Net-(U1-XO32MP)") (class "Default")
      (node (ref "C6") (pin "2") (pinfunction "2_2") (pintype "passive"))
      (node (ref "U1") (pin "E1") (pinfunction "XO32MP_E1") (pintype "bidirectional"))
      (node (ref "Y1") (pin "3") (pinfunction "2_3") (pintype "passive"))
    )
    (net (code "68") (name "VDD") (class "Default")
      (node (ref "C12") (pin "1") (pinfunction "1_1") (pintype "passive"))
      (node (ref "C13") (pin "1") (pinfunction "1_1") (pintype "passive"))
      (node (ref "C14") (pin "1") (pinfunction "1_1") (pintype "passive"))
      (node (ref "C15") (pin "1") (pinfunction "1_1") (pintype "passive"))
      (node (ref "C16") (pin "1") (pinfunction "1_1") (pintype "passive"))
      (node (ref "J36") (pin "1") (pinfunction "1_1") (pintype "bidirectional"))
      (node (ref "J37") (pin "1") (pinfunction "1_1") (pintype "bidirectional"))
      (node (ref "U1") (pin "B1") (pinfunction "VDDP_B1") (pintype "bidirectional"))
      (node (ref "U1") (pin "C2") (pinfunction "VDDB_C2") (pintype "bidirectional"))
      (node (ref "U1") (pin "C3") (pinfunction "VDDA_C3") (pintype "bidirectional"))
      (node (ref "U1") (pin "F6") (pinfunction "VDDH_F6") (pintype "bidirectional"))
      (node (ref "U1") (pin "G2") (pinfunction "VCC_G2") (pintype "bidirectional"))
    )
    (net (code "69") (name "unconnected-(U1-GPIO30-PadF4)") (class "Default")
      (node (ref "U1") (pin "F4") (pinfunction "GPIO30_F4") (pintype "bidirectional"))
    )
    (net (code "70") (name "unconnected-(U1-GPIO46-PadH9)") (class "Default")
      (node (ref "U1") (pin "H9") (pinfunction "GPIO46_H9") (pintype "bidirectional"))
    )
    (net (code "71") (name "unconnected-(U1-GPIO50-PadJ6)") (class "Default")
      (node (ref "U1") (pin "J6") (pinfunction "GPIO50_J6") (pintype "bidirectional"))
    )
    (net (code "72") (name "unconnected-(U1-GPIO51-PadB11)") (class "Default")
      (node (ref "U1") (pin "B11") (pinfunction "GPIO51_B11") (pintype "bidirectional"))
    )
    (net (code "73") (name "unconnected-(U1-GPIO52-PadB12)") (class "Default")
      (node (ref "U1") (pin "B12") (pinfunction "GPIO52_B12") (pintype "bidirectional"))
    )
    (net (code "74") (name "unconnected-(U1-GPIO53-PadD10)") (class "Default")
      (node (ref "U1") (pin "D10") (pinfunction "GPIO53_D10") (pintype "bidirectional"))
    )
    (net (code "75") (name "unconnected-(U1-GPIO54-PadC10)") (class "Default")
      (node (ref "U1") (pin "C10") (pinfunction "GPIO54_C10") (pintype "bidirectional"))
    )
    (net (code "76") (name "unconnected-(U1-GPIO55-PadE11)") (class "Default")
      (node (ref "U1") (pin "E11") (pinfunction "GPIO55_E11") (pintype "bidirectional"))
    )
    (net (code "77") (name "unconnected-(U1-GPIO56-PadD11)") (class "Default")
      (node (ref "U1") (pin "D11") (pinfunction "GPIO56_D11") (pintype "bidirectional"))
    )
    (net (code "78") (name "unconnected-(U1-GPIO57-PadC11)") (class "Default")
      (node (ref "U1") (pin "C11") (pinfunction "GPIO57_C11") (pintype "bidirectional"))
    )
    (net (code "79") (name "unconnected-(U1-GPIO58-PadE12)") (class "Default")
      (node (ref "U1") (pin "E12") (pinfunction "GPIO58_E12") (pintype "bidirectional"))
    )
    (net (code "80") (name "unconnected-(U1-GPIO59-PadD12)") (class "Default")
      (node (ref "U1") (pin "D12") (pinfunction "GPIO59_D12") (pintype "bidirectional"))
    )
    (net (code "81") (name "unconnected-(U1-GPIO60-PadC12)") (class "Default")
      (node (ref "U1") (pin "C12") (pinfunction "GPIO60_C12") (pintype "bidirectional"))
    )
    (net (code "82") (name "unconnected-(U1-GPIO61-PadH6)") (class "Default")
      (node (ref "U1") (pin "H6") (pinfunction "GPIO61_H6") (pintype "bidirectional"))
    )
    (net (code "83") (name "unconnected-(U1-GPIO62-PadG6)") (class "Default")
      (node (ref "U1") (pin "G6") (pinfunction "GPIO62_G6") (pintype "bidirectional"))
    )
    (net (code "84") (name "unconnected-(U1-GPIO63-PadH7)") (class "Default")
      (node (ref "U1") (pin "H7") (pinfunction "GPIO63_H7") (pintype "bidirectional"))
    )
    (net (code "85") (name "unconnected-(U1-GPIO64-PadF12)") (class "Default")
      (node (ref "U1") (pin "F12") (pinfunction "GPIO64_F12") (pintype "bidirectional"))
    )
    (net (code "86") (name "unconnected-(U1-GPIO65-PadF11)") (class "Default")
      (node (ref "U1") (pin "F11") (pinfunction "GPIO65_F11") (pintype "bidirectional"))
    )
    (net (code "87") (name "unconnected-(U1-GPIO66-PadG12)") (class "Default")
      (node (ref "U1") (pin "G12") (pinfunction "GPIO66_G12") (pintype "bidirectional"))
    )
    (net (code "88") (name "unconnected-(U1-GPIO67-PadG11)") (class "Default")
      (node (ref "U1") (pin "G11") (pinfunction "GPIO67_G11") (pintype "bidirectional"))
    )
    (net (code "89") (name "unconnected-(U1-GPIO68-PadG10)") (class "Default")
      (node (ref "U1") (pin "G10") (pinfunction "GPIO68_G10") (pintype "bidirectional"))
    )
    (net (code "90") (name "unconnected-(U1-GPIO69-PadG9)") (class "Default")
      (node (ref "U1") (pin "G9") (pinfunction "GPIO69_G9") (pintype "bidirectional"))
    )
    (net (code "91") (name "unconnected-(U1-GPIO70-PadF9)") (class "Default")
      (node (ref "U1") (pin "F9") (pinfunction "GPIO70_F9") (pintype "bidirectional"))
    )
    (net (code "92") (name "unconnected-(U1-GPIO71-PadJ5)") (class "Default")
      (node (ref "U1") (pin "J5") (pinfunction "GPIO71_J5") (pintype "bidirectional"))
    )
    (net (code "93") (name "unconnected-(U1-GPIO72-PadH5)") (class "Default")
      (node (ref "U1") (pin "H5") (pinfunction "GPIO72_H5") (pintype "bidirectional"))
    )
    (net (code "94") (name "unconnected-(U1-GPIO73-PadG5)") (class "Default")
      (node (ref "U1") (pin "G5") (pinfunction "GPIO73_G5") (pintype "bidirectional"))
    )
    (net (code "95") (name "unconnected-(U1-TXEN-PadH3)") (class "Default")
      (node (ref "U1") (pin "H3") (pinfunction "TXEN_H3") (pintype "bidirectional"))
    )
  )
)
